# RemoteController.net
KiCad netlist of a schematic drawn in EasyEDA Pro
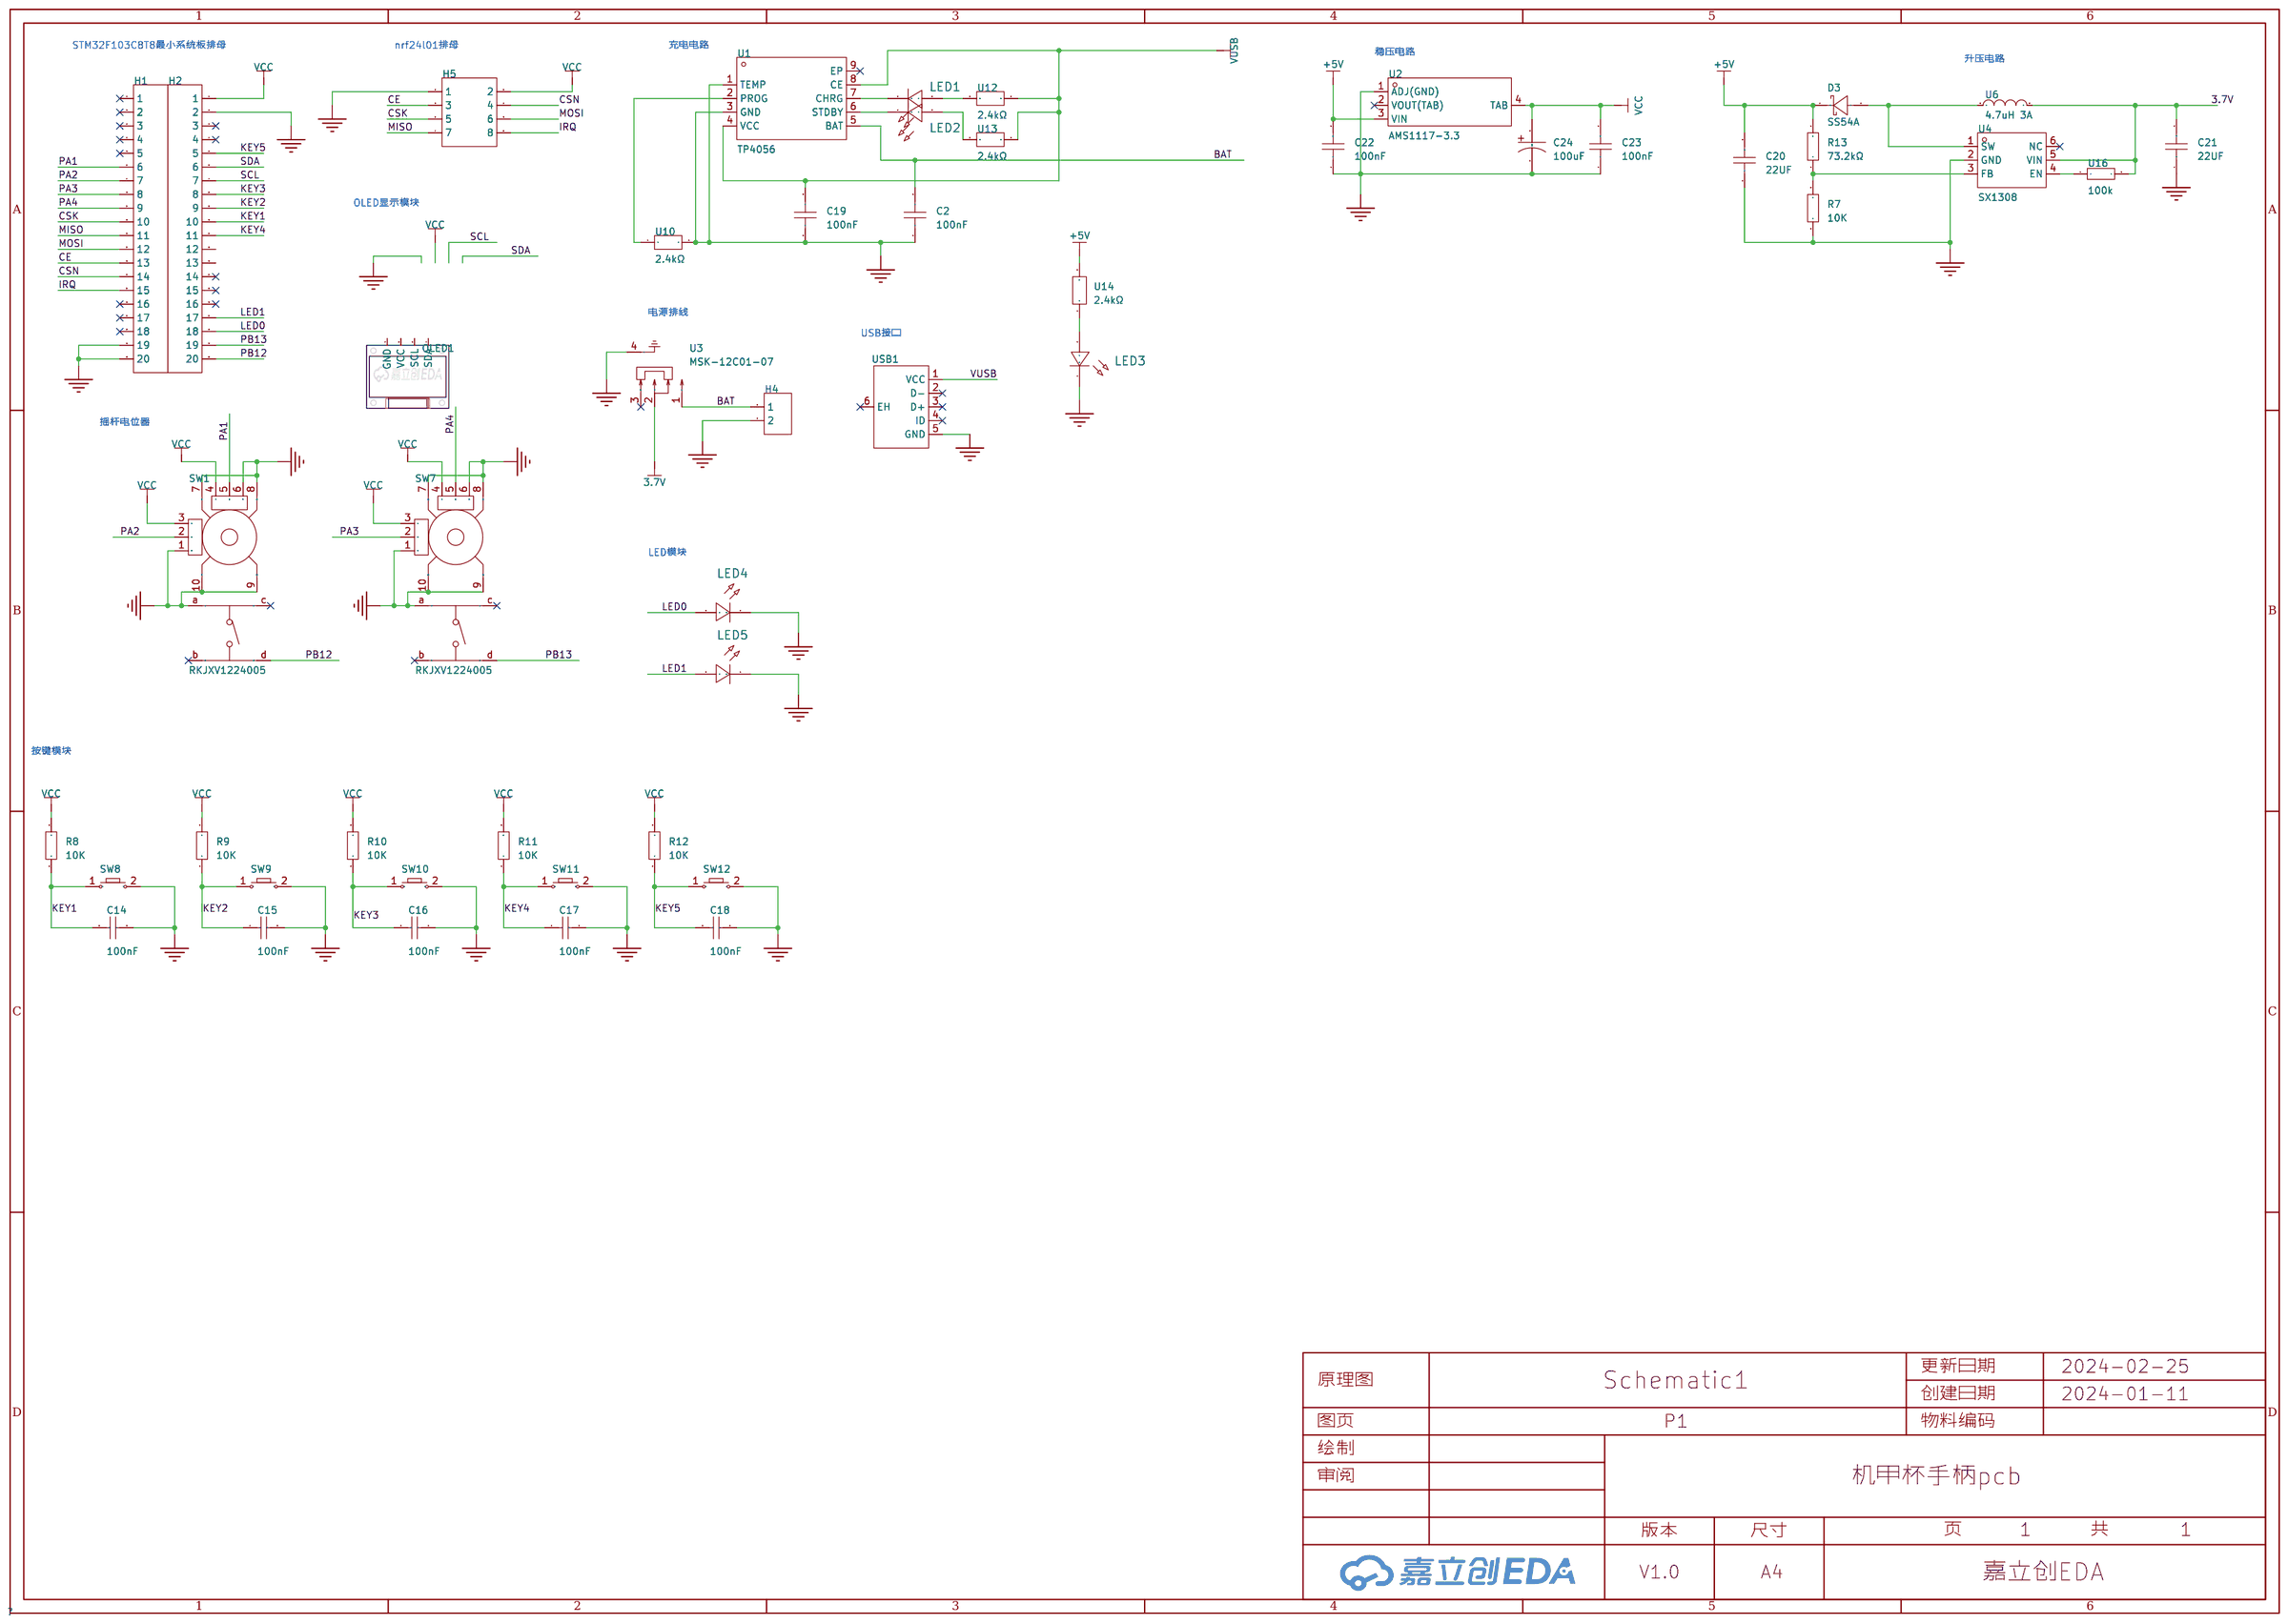
[diagram p0: schematic sheet]

(export (version "E")
  (design (tool "Eeschema 10.0.6"))
  (components
    (comp (ref "C2")
      (value "100nF")
      (footprint "easyedapro:C0805")
      (fields
        (field (name "Manufacturer Part") "CL21B104KCFNNNE")
        (field (name "Manufacturer") "SAMSUNG(三星)")
      )
      (libsource (lib "easyedapro") (part "CapAcitance"))
    )
    (comp (ref "C14")
      (value "100nF")
      (footprint "easyedapro:C0805")
      (description "容值:100nF;精度:±10%;额定电压:100V;材质(温度系数):X7R;")
      (fields
        (field (name "Manufacturer Part") "CL21B104KCFNNNE")
        (field (name "Manufacturer") "SAMSUNG(三星)")
      )
      (libsource (lib "easyedapro") (part "CL21B104KCFNNNE"))
    )
    (comp (ref "C15")
      (value "100nF")
      (footprint "easyedapro:C0805")
      (description "容值:100nF;精度:±10%;额定电压:100V;材质(温度系数):X7R;")
      (fields
        (field (name "Manufacturer Part") "CL21B104KCFNNNE")
        (field (name "Manufacturer") "SAMSUNG(三星)")
      )
      (libsource (lib "easyedapro") (part "CL21B104KCFNNNE"))
    )
    (comp (ref "C16")
      (value "100nF")
      (footprint "easyedapro:C0805")
      (description "容值:100nF;精度:±10%;额定电压:100V;材质(温度系数):X7R;")
      (fields
        (field (name "Manufacturer Part") "CL21B104KCFNNNE")
        (field (name "Manufacturer") "SAMSUNG(三星)")
      )
      (libsource (lib "easyedapro") (part "CL21B104KCFNNNE"))
    )
    (comp (ref "C17")
      (value "100nF")
      (footprint "easyedapro:C0805")
      (description "容值:100nF;精度:±10%;额定电压:100V;材质(温度系数):X7R;")
      (fields
        (field (name "Manufacturer Part") "CL21B104KCFNNNE")
        (field (name "Manufacturer") "SAMSUNG(三星)")
      )
      (libsource (lib "easyedapro") (part "CL21B104KCFNNNE"))
    )
    (comp (ref "C18")
      (value "100nF")
      (footprint "easyedapro:C0805")
      (description "容值:100nF;精度:±10%;额定电压:100V;材质(温度系数):X7R;")
      (fields
        (field (name "Manufacturer Part") "CL21B104KCFNNNE")
        (field (name "Manufacturer") "SAMSUNG(三星)")
      )
      (libsource (lib "easyedapro") (part "CL21B104KCFNNNE"))
    )
    (comp (ref "C19")
      (value "100nF")
      (footprint "easyedapro:C0805")
      (fields
        (field (name "Manufacturer Part") "CL21B104KCFNNNE")
        (field (name "Manufacturer") "SAMSUNG(三星)")
      )
      (libsource (lib "easyedapro") (part "CapAcitance"))
    )
    (comp (ref "C20")
      (value "22UF")
      (footprint "easyedapro:C1206")
      (libsource (lib "easyedapro") (part "22UF_C9900008064"))
    )
    (comp (ref "C21")
      (value "22UF")
      (footprint "easyedapro:C1206")
      (libsource (lib "easyedapro") (part "22UF_C9900008064"))
    )
    (comp (ref "C22")
      (value "100nF")
      (footprint "easyedapro:C0603")
      (description "容值:100nF;精度:±10%;额定电压:50V;材质(温度系数):X7R;")
      (fields
        (field (name "Manufacturer Part") "CC0603KRX7R9BB104")
        (field (name "Manufacturer") "YAGEO(国巨)")
      )
      (libsource (lib "easyedapro") (part "CC0603KRX7R9BB104"))
    )
    (comp (ref "C23")
      (value "100nF")
      (footprint "easyedapro:C0603")
      (description "容值:100nF;精度:±10%;额定电压:50V;材质(温度系数):X7R;")
      (fields
        (field (name "Manufacturer Part") "CC0603KRX7R9BB104")
        (field (name "Manufacturer") "YAGEO(国巨)")
      )
      (libsource (lib "easyedapro") (part "CC0603KRX7R9BB104"))
    )
    (comp (ref "C24")
      (value "100uF")
      (footprint "easyedapro:CASE-D_7343")
      (description "容值:100uF;精度:±20%;额定电压:6.3V;等效串联电阻:400mΩ@100kHz;")
      (fields (field (name "Manufacturer Part") "NOJD107M006RWJ") (field (name "Manufacturer") "Kyocera AVX"))
      (libsource (lib "easyedapro") (part "NOJD107M006RWJ"))
    )
    (comp (ref "D3")
      (value "SS54A")
      (footprint "easyedapro:SMA_L4.2-W2.6-LS5.1-RD")
      (description "二极管配置:独立式;正向压降(Vf):550mV@5A;直流反向耐压(Vr):40V;平均整流电流(Io):5A;")
      (fields (field (name "Manufacturer") "FUXINSEMI(富芯森美)"))
      (libsource (lib "easyedapro") (part "SS54A"))
    )
    (comp (ref "H1")
      (value "~")
      (footprint "easyedapro:HDR-TH_20P-P2.54-V-F")
      (libsource (lib "easyedapro") (part "HDR-F_2.54_1x20P"))
    )
    (comp (ref "H2")
      (value "~")
      (footprint "easyedapro:HDR-TH_20P-P2.54-V-F")
      (libsource (lib "easyedapro") (part "HDR-F_2.54_1x20P"))
    )
    (comp (ref "H4")
      (value "~")
      (footprint "easyedapro:HDR-TH_2P-P2.54-V-F")
      (libsource (lib "easyedapro") (part "Header-Female-2.54_1x2"))
    )
    (comp (ref "H5")
      (value "~")
      (footprint "easyedapro:HDR-TH_8P-P2.54-V-F-R2-C4-S2.54-1")
      (libsource (lib "easyedapro") (part "HDR-F-2.54_2x4"))
    )
    (comp (ref "LED1")
      (value "~")
      (footprint "easyedapro:LED_0603")
      (libsource (lib "easyedapro") (part "LED_R"))
    )
    (comp (ref "LED2")
      (value "~")
      (footprint "easyedapro:LED_0603")
      (libsource (lib "easyedapro") (part "LED_R"))
    )
    (comp (ref "LED3")
      (value "~")
      (footprint "easyedapro:LED_0603")
      (libsource (lib "easyedapro") (part "LED_R"))
    )
    (comp (ref "LED4")
      (value "~")
      (footprint "easyedapro:LED_0603")
      (libsource (lib "easyedapro") (part "LED_R"))
    )
    (comp (ref "LED5")
      (value "~")
      (footprint "easyedapro:LED_0603")
      (libsource (lib "easyedapro") (part "LED_R"))
    )
    (comp (ref "OLED1")
      (value "~")
      (footprint "easyedapro:0.96OLED_4P")
      (libsource (lib "easyedapro") (part "0.96OLED模块_4P"))
    )
    (comp (ref "R7") (value "10K") (footprint "easyedapro:R1206") (libsource (lib "easyedapro") (part "电阻")))
    (comp (ref "R8") (value "10K") (footprint "easyedapro:R1206") (libsource (lib "easyedapro") (part "电阻")))
    (comp (ref "R9") (value "10K") (footprint "easyedapro:R1206") (libsource (lib "easyedapro") (part "电阻")))
    (comp (ref "R10") (value "10K") (footprint "easyedapro:R1206") (libsource (lib "easyedapro") (part "电阻")))
    (comp (ref "R11") (value "10K") (footprint "easyedapro:R1206") (libsource (lib "easyedapro") (part "电阻")))
    (comp (ref "R12") (value "10K") (footprint "easyedapro:R1206") (libsource (lib "easyedapro") (part "电阻")))
    (comp (ref "R13")
      (value "73.2kΩ")
      (footprint "easyedapro:R0603")
      (description "电阻类型:厚膜电阻;阻值:73.2kΩ;精度:±1%;功率:100mW;最大工作电压:75V;温度系数:±100ppm/°C;")
      (fields (field (name "Manufacturer Part") "AC0603FR-0773K2L") (field (name "Manufacturer") "YAGEO(国巨)"))
      (libsource (lib "easyedapro") (part "AC0603FR-0773K2L"))
    )
    (comp (ref "SW1")
      (value "RKJXV1224005")
      (footprint "easyedapro:SW-TH_RKJXV1224005")
      (description "操纵杆复位 中央按动开关 适用于航模玩具遥控器电位器、3D摇杆PS4手柄游戏机、无人机摇杆电位器、工业控制器")
      (fields (field (name "Manufacturer") "ALPSALPINE(阿尔卑斯阿尔派)"))
      (libsource (lib "easyedapro") (part "RKJXV1224005"))
    )
    (comp (ref "SW7")
      (value "RKJXV1224005")
      (footprint "easyedapro:SW-TH_RKJXV1224005")
      (description "操纵杆复位 中央按动开关 适用于航模玩具遥控器电位器、3D摇杆PS4手柄游戏机、无人机摇杆电位器、工业控制器")
      (fields (field (name "Manufacturer") "ALPSALPINE(阿尔卑斯阿尔派)"))
      (libsource (lib "easyedapro") (part "RKJXV1224005"))
    )
    (comp (ref "SW8")
      (value "~")
      (footprint "easyedapro:Key_SMD_3x4x2")
      (libsource (lib "easyedapro") (part "轻触按键x2"))
    )
    (comp (ref "SW9")
      (value "~")
      (footprint "easyedapro:Key_SMD_3x4x2")
      (libsource (lib "easyedapro") (part "轻触按键x2"))
    )
    (comp (ref "SW10")
      (value "~")
      (footprint "easyedapro:Key_SMD_3x4x2")
      (libsource (lib "easyedapro") (part "轻触按键x2"))
    )
    (comp (ref "SW11")
      (value "~")
      (footprint "easyedapro:Key_SMD_3x4x2")
      (libsource (lib "easyedapro") (part "轻触按键x2"))
    )
    (comp (ref "SW12")
      (value "~")
      (footprint "easyedapro:Key_SMD_3x4x2")
      (libsource (lib "easyedapro") (part "轻触按键x2"))
    )
    (comp (ref "U1")
      (value "TP4056")
      (footprint "easyedapro:ESOP-8_L4.9-W3.9-P1.27-LS6.0-BL-EP")
      (libsource (lib "easyedapro") (part "TP4056_C9900002169"))
    )
    (comp (ref "U2")
      (value "AMS1117-3.3")
      (footprint "easyedapro:SOT-223-4_L6.5-W3.5-P2.30-LS7.0-BR")
      (description "输出类型:固定;最大输入电压:18V;输出电压:3.3V;输出电流:1A;电源纹波抑制比(PSRR):60dB@(120Hz);输出极性:正;")
      (fields (field (name "Manufacturer") "UMW(友台半导体)"))
      (libsource (lib "easyedapro") (part "AMS1117-3.3_C347222"))
    )
    (comp (ref "U3")
      (value "MSK-12C01-07")
      (footprint "easyedapro:SW-SMD_MSK12CO2-BDM")
      (libsource (lib "easyedapro") (part "MSK-12C01-07"))
    )
    (comp (ref "U4")
      (value "SX1308")
      (footprint "easyedapro:SOT-23-6_L2.9-W1.6-P0.95-LS2.8-BL")
      (description "功能类型:升压型;同步整流:否;输出通道数:1;拓扑结构:升压式;输入电压:2V~24V;输出电压:28V;输出电流(最大值):-;开关频率:1.2MHz;")
      (fields (field (name "Manufacturer") "SX(硕芯科技)"))
      (libsource (lib "easyedapro") (part "SX1308"))
    )
    (comp (ref "U6")
      (value "4.7uH 3A")
      (footprint "easyedapro:IND-SMD_L7.3-W7.3_GSDRH74P")
      (libsource (lib "easyedapro") (part "4.7UH 3A"))
    )
    (comp (ref "U10")
      (value "2.4kΩ")
      (footprint "easyedapro:R0603")
      (description "电阻类型:薄膜电阻;阻值:2.4kΩ;精度:±0.1%;功率:100mW;最大工作电压:100V;温度系数:±10ppm/°C;")
      (fields (field (name "Manufacturer Part") "PTFR0603B2K40N9") (field (name "Manufacturer") "RESI(开步睿思）"))
      (libsource (lib "easyedapro") (part "PTFR0603B2K40N9"))
    )
    (comp (ref "U12")
      (value "2.4kΩ")
      (footprint "easyedapro:R0603")
      (description "电阻类型:薄膜电阻;阻值:2.4kΩ;精度:±0.1%;功率:100mW;最大工作电压:100V;温度系数:±10ppm/°C;")
      (fields (field (name "Manufacturer Part") "PTFR0603B2K40N9") (field (name "Manufacturer") "RESI(开步睿思）"))
      (libsource (lib "easyedapro") (part "PTFR0603B2K40N9"))
    )
    (comp (ref "U13")
      (value "2.4kΩ")
      (footprint "easyedapro:R0603")
      (description "电阻类型:薄膜电阻;阻值:2.4kΩ;精度:±0.1%;功率:100mW;最大工作电压:100V;温度系数:±10ppm/°C;")
      (fields (field (name "Manufacturer Part") "PTFR0603B2K40N9") (field (name "Manufacturer") "RESI(开步睿思）"))
      (libsource (lib "easyedapro") (part "PTFR0603B2K40N9"))
    )
    (comp (ref "U14")
      (value "2.4kΩ")
      (footprint "easyedapro:R0603")
      (description "电阻类型:薄膜电阻;阻值:2.4kΩ;精度:±0.1%;功率:100mW;最大工作电压:100V;温度系数:±10ppm/°C;")
      (fields (field (name "Manufacturer Part") "PTFR0603B2K40N9") (field (name "Manufacturer") "RESI(开步睿思）"))
      (libsource (lib "easyedapro") (part "PTFR0603B2K40N9"))
    )
    (comp (ref "U16")
      (value "100k")
      (footprint "easyedapro:R0603")
      (libsource (lib "easyedapro") (part "100K"))
    )
    (comp (ref "USB1")
      (value "~")
      (footprint "easyedapro:USB_Micro")
      (libsource (lib "easyedapro") (part "USB_Micro"))
    )
  )
  (nets
    (net (code "1") (name "+5V") (class "Default")
      (node (ref "C20") (pin "2") (pinfunction "2_2") (pintype "input"))
      (node (ref "C22") (pin "2") (pinfunction "2_2") (pintype "unspecified"))
      (node (ref "D3") (pin "1") (pinfunction "C_1") (pintype "unspecified"))
      (node (ref "R13") (pin "2") (pinfunction "2_2") (pintype "unspecified"))
      (node (ref "U14") (pin "2") (pinfunction "2_2") (pintype "unspecified"))
      (node (ref "U2") (pin "3") (pinfunction "VIN_3") (pintype "unspecified"))
    )
    (net (code "2") (name "/BAT") (class "Default")
      (node (ref "C2") (pin "2") (pinfunction "2_2") (pintype "input"))
      (node (ref "H4") (pin "1") (pinfunction "1_1") (pintype "input"))
      (node (ref "U1") (pin "5") (pinfunction "BAT_5") (pintype "input"))
      (node (ref "U3") (pin "1") (pinfunction "1_1") (pintype "input"))
    )
    (net (code "3") (name "/CE") (class "Default")
      (node (ref "H1") (pin "13") (pinfunction "13_13") (pintype "input"))
      (node (ref "H5") (pin "3") (pinfunction "3_3") (pintype "input"))
    )
    (net (code "4") (name "/CSK") (class "Default")
      (node (ref "H1") (pin "10") (pinfunction "10_10") (pintype "input"))
      (node (ref "H5") (pin "5") (pinfunction "5_5") (pintype "input"))
    )
    (net (code "5") (name "/CSN") (class "Default")
      (node (ref "H1") (pin "14") (pinfunction "14_14") (pintype "input"))
      (node (ref "H5") (pin "4") (pinfunction "4_4") (pintype "input"))
    )
    (net (code "6") (name "/IRQ") (class "Default")
      (node (ref "H1") (pin "15") (pinfunction "15_15") (pintype "input"))
      (node (ref "H5") (pin "8") (pinfunction "8_8") (pintype "input"))
    )
    (net (code "7") (name "/KEY1") (class "Default")
      (node (ref "C14") (pin "1") (pinfunction "1_1") (pintype "input"))
      (node (ref "H2") (pin "10") (pinfunction "10_10") (pintype "input"))
      (node (ref "R8") (pin "1") (pinfunction "1_1") (pintype "input"))
      (node (ref "SW8") (pin "1") (pinfunction "1_1") (pintype "input"))
    )
    (net (code "8") (name "/KEY2") (class "Default")
      (node (ref "C15") (pin "1") (pinfunction "1_1") (pintype "input"))
      (node (ref "H2") (pin "9") (pinfunction "9_9") (pintype "input"))
      (node (ref "R9") (pin "1") (pinfunction "1_1") (pintype "input"))
      (node (ref "SW9") (pin "1") (pinfunction "1_1") (pintype "input"))
    )
    (net (code "9") (name "/KEY3") (class "Default")
      (node (ref "C16") (pin "1") (pinfunction "1_1") (pintype "input"))
      (node (ref "H2") (pin "8") (pinfunction "8_8") (pintype "input"))
      (node (ref "R10") (pin "1") (pinfunction "1_1") (pintype "input"))
      (node (ref "SW10") (pin "1") (pinfunction "1_1") (pintype "input"))
    )
    (net (code "10") (name "/KEY4") (class "Default")
      (node (ref "C17") (pin "1") (pinfunction "1_1") (pintype "input"))
      (node (ref "H2") (pin "11") (pinfunction "11_11") (pintype "input"))
      (node (ref "R11") (pin "1") (pinfunction "1_1") (pintype "input"))
      (node (ref "SW11") (pin "1") (pinfunction "1_1") (pintype "input"))
    )
    (net (code "11") (name "/KEY5") (class "Default")
      (node (ref "C18") (pin "1") (pinfunction "1_1") (pintype "input"))
      (node (ref "H2") (pin "5") (pinfunction "5_5") (pintype "input"))
      (node (ref "R12") (pin "1") (pinfunction "1_1") (pintype "input"))
      (node (ref "SW12") (pin "1") (pinfunction "1_1") (pintype "input"))
    )
    (net (code "12") (name "/LED0") (class "Default")
      (node (ref "H2") (pin "18") (pinfunction "18_18") (pintype "input"))
      (node (ref "LED4") (pin "2") (pinfunction "A_2") (pintype "input"))
    )
    (net (code "13") (name "/LED1") (class "Default")
      (node (ref "H2") (pin "17") (pinfunction "17_17") (pintype "input"))
      (node (ref "LED5") (pin "2") (pinfunction "A_2") (pintype "input"))
    )
    (net (code "14") (name "/MISO") (class "Default")
      (node (ref "H1") (pin "11") (pinfunction "11_11") (pintype "input"))
      (node (ref "H5") (pin "7") (pinfunction "7_7") (pintype "input"))
    )
    (net (code "15") (name "/MOSI") (class "Default")
      (node (ref "H1") (pin "12") (pinfunction "12_12") (pintype "input"))
      (node (ref "H5") (pin "6") (pinfunction "6_6") (pintype "input"))
    )
    (net (code "16") (name "/PA1") (class "Default")
      (node (ref "H1") (pin "6") (pinfunction "6_6") (pintype "input"))
      (node (ref "SW1") (pin "5") (pinfunction "DTA_5") (pintype "unspecified"))
    )
    (net (code "17") (name "/PA2") (class "Default")
      (node (ref "H1") (pin "7") (pinfunction "7_7") (pintype "input"))
      (node (ref "SW1") (pin "2") (pinfunction "DTA_2") (pintype "unspecified"))
    )
    (net (code "18") (name "/PA3") (class "Default")
      (node (ref "H1") (pin "8") (pinfunction "8_8") (pintype "input"))
      (node (ref "SW7") (pin "2") (pinfunction "DTA_2") (pintype "unspecified"))
    )
    (net (code "19") (name "/PA4") (class "Default")
      (node (ref "H1") (pin "9") (pinfunction "9_9") (pintype "input"))
      (node (ref "SW7") (pin "5") (pinfunction "DTA_5") (pintype "unspecified"))
    )
    (net (code "20") (name "/PB12") (class "Default")
      (node (ref "H2") (pin "20") (pinfunction "20_20") (pintype "input"))
      (node (ref "SW1") (pin "d") (pinfunction "d_d") (pintype "unspecified"))
    )
    (net (code "21") (name "/PB13") (class "Default")
      (node (ref "H2") (pin "19") (pinfunction "19_19") (pintype "input"))
      (node (ref "SW7") (pin "d") (pinfunction "d_d") (pintype "unspecified"))
    )
    (net (code "22") (name "/SCL") (class "Default")
      (node (ref "H2") (pin "7") (pinfunction "7_7") (pintype "input"))
    )
    (net (code "23") (name "/SDA") (class "Default")
      (node (ref "H2") (pin "6") (pinfunction "6_6") (pintype "input"))
    )
    (net (code "24") (name "3.7V") (class "Default")
      (node (ref "C21") (pin "2") (pinfunction "2_2") (pintype "input"))
      (node (ref "U16") (pin "2") (pinfunction "2_2") (pintype "input"))
      (node (ref "U3") (pin "2") (pinfunction "2_2") (pintype "input"))
      (node (ref "U4") (pin "5") (pinfunction "VIN_5") (pintype "input"))
      (node (ref "U6") (pin "2") (pinfunction "2_2") (pintype "input"))
    )
    (net (code "25") (name "GND") (class "Default")
      (node (ref "C14") (pin "2") (pinfunction "2_2") (pintype "input"))
      (node (ref "C15") (pin "2") (pinfunction "2_2") (pintype "input"))
      (node (ref "C16") (pin "2") (pinfunction "2_2") (pintype "input"))
      (node (ref "C17") (pin "2") (pinfunction "2_2") (pintype "input"))
      (node (ref "C18") (pin "2") (pinfunction "2_2") (pintype "input"))
      (node (ref "C19") (pin "1") (pinfunction "1_1") (pintype "input"))
      (node (ref "C2") (pin "1") (pinfunction "1_1") (pintype "input"))
      (node (ref "C20") (pin "1") (pinfunction "1_1") (pintype "input"))
      (node (ref "C21") (pin "1") (pinfunction "1_1") (pintype "input"))
      (node (ref "C22") (pin "1") (pinfunction "1_1") (pintype "unspecified"))
      (node (ref "C23") (pin "1") (pinfunction "1_1") (pintype "unspecified"))
      (node (ref "C24") (pin "2") (pinfunction "2_2") (pintype "input"))
      (node (ref "H1") (pin "19") (pinfunction "19_19") (pintype "input"))
      (node (ref "H1") (pin "20") (pinfunction "20_20") (pintype "input"))
      (node (ref "H2") (pin "2") (pinfunction "2_2") (pintype "input"))
      (node (ref "H4") (pin "2") (pinfunction "2_2") (pintype "input"))
      (node (ref "H5") (pin "1") (pinfunction "1_1") (pintype "input"))
      (node (ref "LED3") (pin "1") (pinfunction "C_1") (pintype "input"))
      (node (ref "LED4") (pin "1") (pinfunction "C_1") (pintype "input"))
      (node (ref "LED5") (pin "1") (pinfunction "C_1") (pintype "input"))
      (node (ref "R7") (pin "1") (pinfunction "1_1") (pintype "input"))
      (node (ref "SW1") (pin "1") (pinfunction "B_1") (pintype "unspecified"))
      (node (ref "SW1") (pin "10") (pinfunction "GND_10") (pintype "unspecified"))
      (node (ref "SW1") (pin "6") (pinfunction "B_6") (pintype "unspecified"))
      (node (ref "SW1") (pin "7") (pinfunction "GND_7") (pintype "unspecified"))
      (node (ref "SW1") (pin "8") (pinfunction "GND_8") (pintype "unspecified"))
      (node (ref "SW1") (pin "9") (pinfunction "GND_9") (pintype "unspecified"))
      (node (ref "SW1") (pin "a") (pinfunction "a_a") (pintype "unspecified"))
      (node (ref "SW10") (pin "2") (pinfunction "2_2") (pintype "input"))
      (node (ref "SW11") (pin "2") (pinfunction "2_2") (pintype "input"))
      (node (ref "SW12") (pin "2") (pinfunction "2_2") (pintype "input"))
      (node (ref "SW7") (pin "1") (pinfunction "B_1") (pintype "unspecified"))
      (node (ref "SW7") (pin "10") (pinfunction "GND_10") (pintype "unspecified"))
      (node (ref "SW7") (pin "6") (pinfunction "B_6") (pintype "unspecified"))
      (node (ref "SW7") (pin "7") (pinfunction "GND_7") (pintype "unspecified"))
      (node (ref "SW7") (pin "8") (pinfunction "GND_8") (pintype "unspecified"))
      (node (ref "SW7") (pin "9") (pinfunction "GND_9") (pintype "unspecified"))
      (node (ref "SW7") (pin "a") (pinfunction "a_a") (pintype "unspecified"))
      (node (ref "SW8") (pin "2") (pinfunction "2_2") (pintype "input"))
      (node (ref "SW9") (pin "2") (pinfunction "2_2") (pintype "input"))
      (node (ref "U1") (pin "1") (pinfunction "TEMP_1") (pintype "input"))
      (node (ref "U1") (pin "3") (pinfunction "GND_3") (pintype "input"))
      (node (ref "U10") (pin "2") (pinfunction "2_2") (pintype "unspecified"))
      (node (ref "U2") (pin "1") (pinfunction "ADJ(GND)_1") (pintype "unspecified"))
      (node (ref "U3") (pin "4") (pinfunction "4_4") (pintype "input"))
      (node (ref "U4") (pin "2") (pinfunction "GND_2") (pintype "input"))
      (node (ref "USB1") (pin "5") (pinfunction "GND_5") (pintype "input"))
    )
    (net (code "26") (name "Net-(D3-A)") (class "Default")
      (node (ref "D3") (pin "2") (pinfunction "A_2") (pintype "unspecified"))
      (node (ref "U4") (pin "1") (pinfunction "SW_1") (pintype "input"))
      (node (ref "U6") (pin "1") (pinfunction "1_1") (pintype "input"))
    )
    (net (code "27") (name "Net-(LED1-A)") (class "Default")
      (node (ref "LED1") (pin "2") (pinfunction "A_2") (pintype "input"))
      (node (ref "U12") (pin "1") (pinfunction "1_1") (pintype "unspecified"))
    )
    (net (code "28") (name "Net-(LED1-C)") (class "Default")
      (node (ref "LED1") (pin "1") (pinfunction "C_1") (pintype "input"))
      (node (ref "U1") (pin "7") (pinfunction "CHRG_7") (pintype "input"))
    )
    (net (code "29") (name "Net-(LED2-A)") (class "Default")
      (node (ref "LED2") (pin "2") (pinfunction "A_2") (pintype "input"))
      (node (ref "U13") (pin "1") (pinfunction "1_1") (pintype "unspecified"))
    )
    (net (code "30") (name "Net-(LED2-C)") (class "Default")
      (node (ref "LED2") (pin "1") (pinfunction "C_1") (pintype "input"))
      (node (ref "U1") (pin "6") (pinfunction "STDBY_6") (pintype "input"))
    )
    (net (code "31") (name "Net-(LED3-A)") (class "Default")
      (node (ref "LED3") (pin "2") (pinfunction "A_2") (pintype "input"))
      (node (ref "U14") (pin "1") (pinfunction "1_1") (pintype "unspecified"))
    )
    (net (code "32") (name "Net-(U1-PROG)") (class "Default")
      (node (ref "U1") (pin "2") (pinfunction "PROG_2") (pintype "input"))
      (node (ref "U10") (pin "1") (pinfunction "1_1") (pintype "unspecified"))
    )
    (net (code "33") (name "Net-(U4-EN)") (class "Default")
      (node (ref "U16") (pin "1") (pinfunction "1_1") (pintype "input"))
      (node (ref "U4") (pin "4") (pinfunction "EN_4") (pintype "input"))
    )
    (net (code "34") (name "Net-(U4-FB)") (class "Default")
      (node (ref "R13") (pin "1") (pinfunction "1_1") (pintype "unspecified"))
      (node (ref "R7") (pin "2") (pinfunction "2_2") (pintype "input"))
      (node (ref "U4") (pin "3") (pinfunction "FB_3") (pintype "input"))
    )
    (net (code "35") (name "VCC") (class "Default")
      (node (ref "C23") (pin "2") (pinfunction "2_2") (pintype "unspecified"))
      (node (ref "C24") (pin "1") (pinfunction "1_1") (pintype "input"))
      (node (ref "H2") (pin "1") (pinfunction "1_1") (pintype "input"))
      (node (ref "H5") (pin "2") (pinfunction "2_2") (pintype "input"))
      (node (ref "R10") (pin "2") (pinfunction "2_2") (pintype "input"))
      (node (ref "R11") (pin "2") (pinfunction "2_2") (pintype "input"))
      (node (ref "R12") (pin "2") (pinfunction "2_2") (pintype "input"))
      (node (ref "R8") (pin "2") (pinfunction "2_2") (pintype "input"))
      (node (ref "R9") (pin "2") (pinfunction "2_2") (pintype "input"))
      (node (ref "SW1") (pin "3") (pinfunction "A_3") (pintype "unspecified"))
      (node (ref "SW1") (pin "4") (pinfunction "A_4") (pintype "unspecified"))
      (node (ref "SW7") (pin "3") (pinfunction "A_3") (pintype "unspecified"))
      (node (ref "SW7") (pin "4") (pinfunction "A_4") (pintype "unspecified"))
      (node (ref "U2") (pin "4") (pinfunction "TAB_4") (pintype "unspecified"))
    )
    (net (code "36") (name "VUSB") (class "Default")
      (node (ref "C19") (pin "2") (pinfunction "2_2") (pintype "input"))
      (node (ref "U1") (pin "4") (pinfunction "VCC_4") (pintype "input"))
      (node (ref "U1") (pin "8") (pinfunction "CE_8") (pintype "input"))
      (node (ref "U12") (pin "2") (pinfunction "2_2") (pintype "unspecified"))
      (node (ref "U13") (pin "2") (pinfunction "2_2") (pintype "unspecified"))
      (node (ref "USB1") (pin "1") (pinfunction "VCC_1") (pintype "input"))
    )
    (net (code "37") (name "unconnected-(H1-Pad1)") (class "Default")
      (node (ref "H1") (pin "1") (pinfunction "1_1") (pintype "input+no_connect"))
    )
    (net (code "38") (name "unconnected-(H1-Pad2)") (class "Default")
      (node (ref "H1") (pin "2") (pinfunction "2_2") (pintype "input+no_connect"))
    )
    (net (code "39") (name "unconnected-(H1-Pad3)") (class "Default")
      (node (ref "H1") (pin "3") (pinfunction "3_3") (pintype "input+no_connect"))
    )
    (net (code "40") (name "unconnected-(H1-Pad4)") (class "Default")
      (node (ref "H1") (pin "4") (pinfunction "4_4") (pintype "input+no_connect"))
    )
    (net (code "41") (name "unconnected-(H1-Pad5)") (class "Default")
      (node (ref "H1") (pin "5") (pinfunction "5_5") (pintype "input+no_connect"))
    )
    (net (code "42") (name "unconnected-(H1-Pad16)") (class "Default")
      (node (ref "H1") (pin "16") (pinfunction "16_16") (pintype "input+no_connect"))
    )
    (net (code "43") (name "unconnected-(H1-Pad17)") (class "Default")
      (node (ref "H1") (pin "17") (pinfunction "17_17") (pintype "input+no_connect"))
    )
    (net (code "44") (name "unconnected-(H1-Pad18)") (class "Default")
      (node (ref "H1") (pin "18") (pinfunction "18_18") (pintype "input+no_connect"))
    )
    (net (code "45") (name "unconnected-(H2-Pad3)") (class "Default")
      (node (ref "H2") (pin "3") (pinfunction "3_3") (pintype "input+no_connect"))
    )
    (net (code "46") (name "unconnected-(H2-Pad4)") (class "Default")
      (node (ref "H2") (pin "4") (pinfunction "4_4") (pintype "input+no_connect"))
    )
    (net (code "47") (name "unconnected-(H2-Pad12)") (class "Default")
      (node (ref "H2") (pin "12") (pinfunction "12_12") (pintype "input"))
    )
    (net (code "48") (name "unconnected-(H2-Pad13)") (class "Default")
      (node (ref "H2") (pin "13") (pinfunction "13_13") (pintype "input"))
    )
    (net (code "49") (name "unconnected-(H2-Pad14)") (class "Default")
      (node (ref "H2") (pin "14") (pinfunction "14_14") (pintype "input+no_connect"))
    )
    (net (code "50") (name "unconnected-(H2-Pad15)") (class "Default")
      (node (ref "H2") (pin "15") (pinfunction "15_15") (pintype "input+no_connect"))
    )
    (net (code "51") (name "unconnected-(H2-Pad16)") (class "Default")
      (node (ref "H2") (pin "16") (pinfunction "16_16") (pintype "input+no_connect"))
    )
    (net (code "52") (name "unconnected-(OLED1-GND-Pad1)") (class "Default")
      (node (ref "OLED1") (pin "1") (pinfunction "GND_1") (pintype "input"))
    )
    (net (code "53") (name "unconnected-(OLED1-SCL-Pad3)") (class "Default")
      (node (ref "OLED1") (pin "3") (pinfunction "SCL_3") (pintype "input"))
    )
    (net (code "54") (name "unconnected-(OLED1-SDA-Pad4)") (class "Default")
      (node (ref "OLED1") (pin "4") (pinfunction "SDA_4") (pintype "input"))
    )
    (net (code "55") (name "unconnected-(OLED1-VCC-Pad2)") (class "Default")
      (node (ref "OLED1") (pin "2") (pinfunction "VCC_2") (pintype "input"))
    )
    (net (code "56") (name "unconnected-(SW1-Padb)") (class "Default")
      (node (ref "SW1") (pin "b") (pinfunction "b_b") (pintype "unspecified+no_connect"))
    )
    (net (code "57") (name "unconnected-(SW1-Padc)") (class "Default")
      (node (ref "SW1") (pin "c") (pinfunction "c_c") (pintype "unspecified+no_connect"))
    )
    (net (code "58") (name "unconnected-(SW7-Padb)") (class "Default")
      (node (ref "SW7") (pin "b") (pinfunction "b_b") (pintype "unspecified+no_connect"))
    )
    (net (code "59") (name "unconnected-(SW7-Padc)") (class "Default")
      (node (ref "SW7") (pin "c") (pinfunction "c_c") (pintype "unspecified+no_connect"))
    )
    (net (code "60") (name "unconnected-(U1-EP-Pad9)") (class "Default")
      (node (ref "U1") (pin "9") (pinfunction "EP_9") (pintype "input+no_connect"))
    )
    (net (code "61") (name "unconnected-(U2-VOUT(TAB)-Pad2)") (class "Default")
      (node (ref "U2") (pin "2") (pinfunction "VOUT(TAB)_2") (pintype "unspecified+no_connect"))
    )
    (net (code "62") (name "unconnected-(U3-Pad3)") (class "Default")
      (node (ref "U3") (pin "3") (pinfunction "3_3") (pintype "input+no_connect"))
    )
    (net (code "63") (name "unconnected-(U4-NC-Pad6)") (class "Default")
      (node (ref "U4") (pin "6") (pinfunction "NC_6") (pintype "input+no_connect"))
    )
    (net (code "64") (name "unconnected-(USB1-D+-Pad3)") (class "Default")
      (node (ref "USB1") (pin "3") (pinfunction "D+_3") (pintype "input+no_connect"))
    )
    (net (code "65") (name "unconnected-(USB1-D--Pad2)") (class "Default")
      (node (ref "USB1") (pin "2") (pinfunction "D-_2") (pintype "input+no_connect"))
    )
    (net (code "66") (name "unconnected-(USB1-EH-Pad6)") (class "Default")
      (node (ref "USB1") (pin "6") (pinfunction "EH_6") (pintype "input+no_connect"))
    )
    (net (code "67") (name "unconnected-(USB1-ID-Pad4)") (class "Default")
      (node (ref "USB1") (pin "4") (pinfunction "ID_4") (pintype "input+no_connect"))
    )
  )
)
